# segger_adaptor_v1.net
KiCad netlist of a schematic drawn in EAGLE
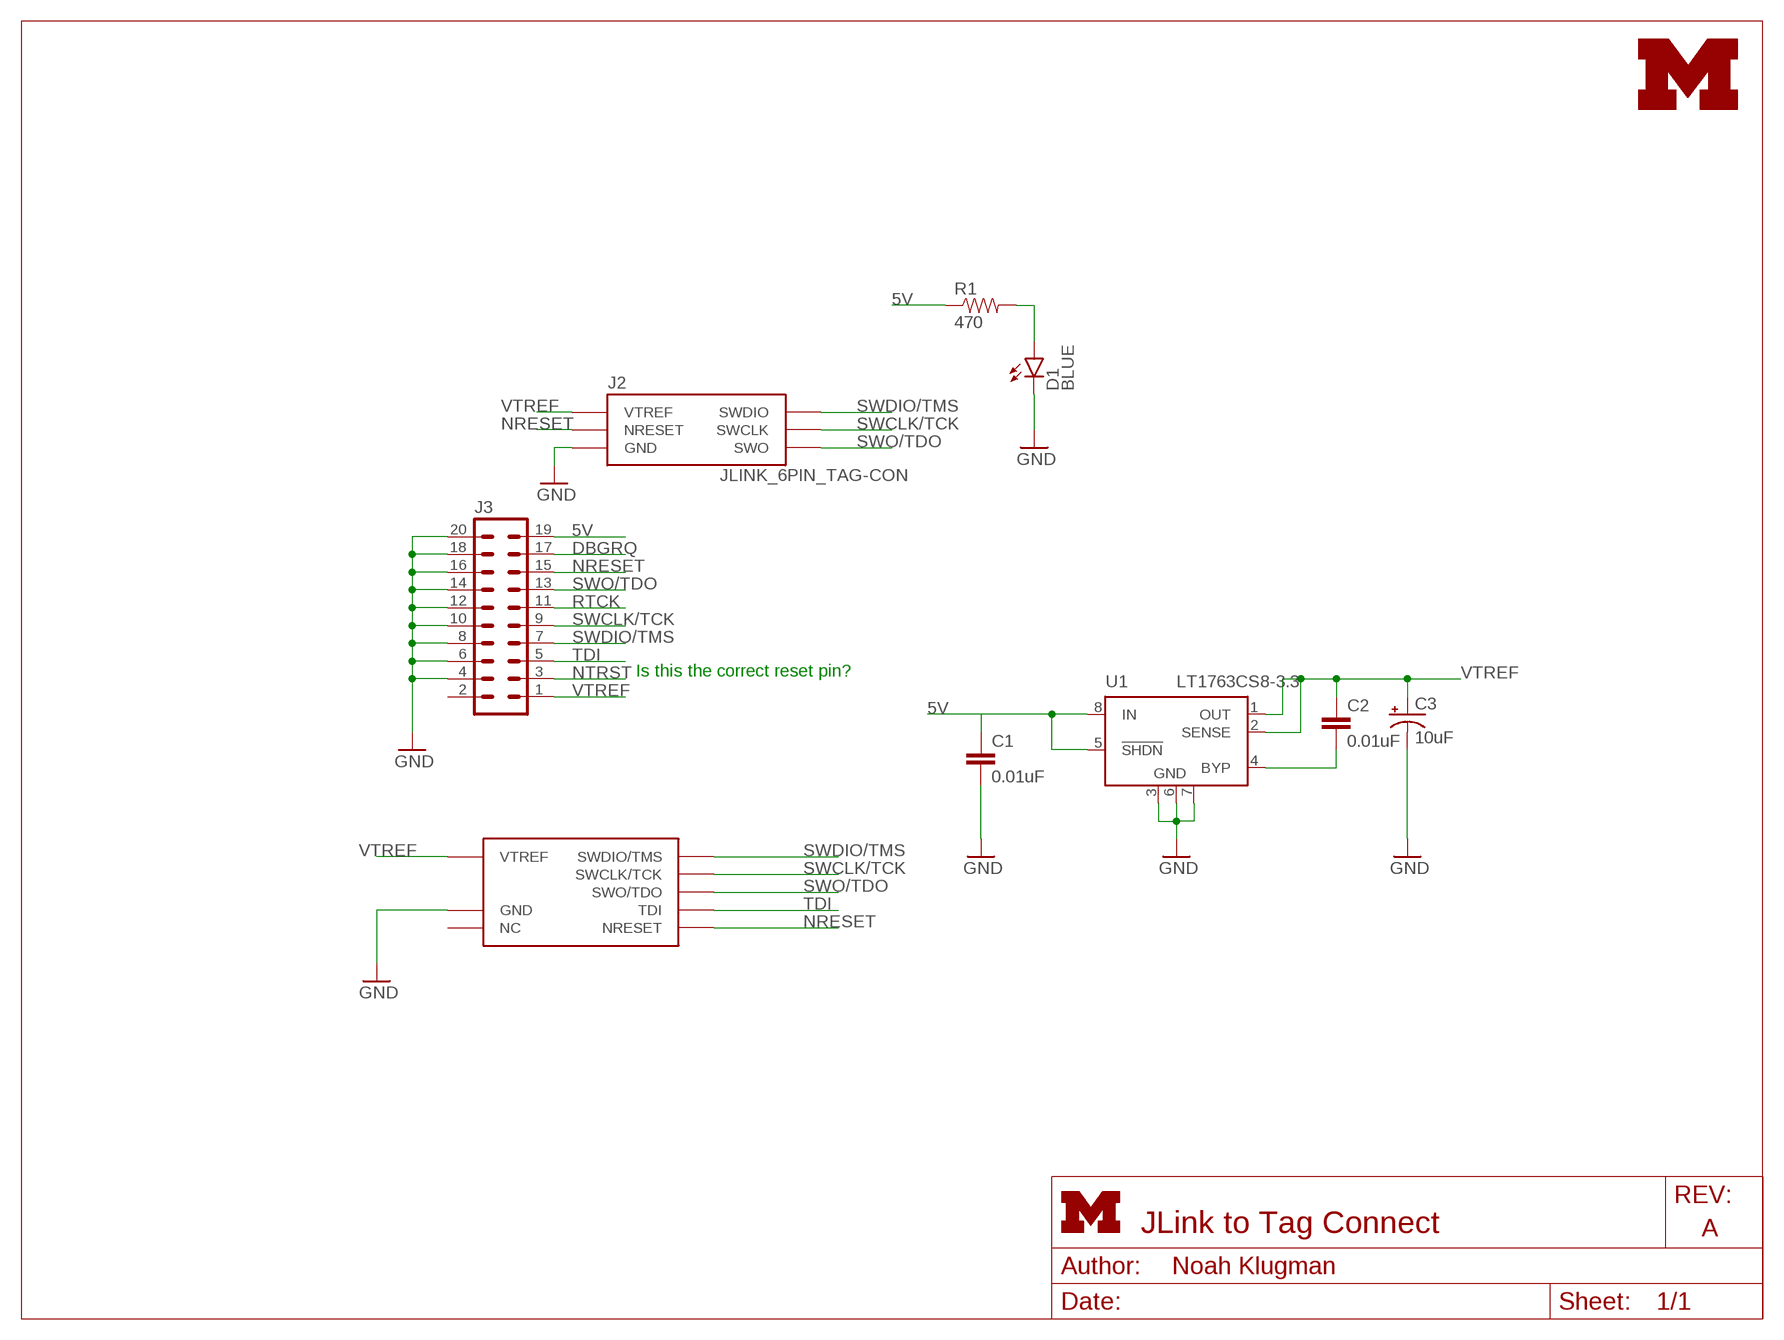
[diagram p0: schematic, sheet 1]

(export (version "E")
  (design (tool "Eeschema 10.0.6"))
  (components
    (comp (ref "C1")
      (value "0.01uF")
      (footprint "eagle-import:C0603")
      (libsource (lib "eagle-import") (part "C-EUC0603"))
    )
    (comp (ref "C2")
      (value "0.01uF")
      (footprint "eagle-import:C0603")
      (libsource (lib "eagle-import") (part "C-EUC0603"))
    )
    (comp (ref "C3")
      (value "10uF")
      (footprint "eagle-import:EIA3216")
      (libsource (lib "eagle-import") (part "CAP_POL1206"))
    )
    (comp (ref "D1")
      (value "BLUE")
      (footprint "eagle-import:LED-0603")
      (libsource (lib "eagle-import") (part "LED-BLUE0603"))
    )
    (comp (ref "J1")
      (value "PINHD-2X5/0.050-NO7")
      (footprint "eagle-import:2X5-0.050-NO7")
      (libsource (lib "eagle-import") (part "PINHD-2X5/0.050-NO7"))
    )
    (comp (ref "J2")
      (value "JLINK_6PIN_TAG-CON")
      (footprint "eagle-import:2X3_MALE_SHROUDED_0.100")
      (libsource (lib "eagle-import") (part "JLINK_6PIN_TAG-CON"))
    )
    (comp (ref "J3")
      (value "ML20")
      (footprint "eagle-import:ML20")
      (libsource (lib "eagle-import") (part "ML20"))
    )
    (comp (ref "LOGO1")
      (value "UMICH_SOLID_SMALL+")
      (footprint "eagle-import:UMICH_SOLID_100MIL")
      (libsource (lib "eagle-import") (part "UMICH_SOLID_SMALL+"))
    )
    (comp (ref "R1")
      (value "470")
      (footprint "eagle-import:0603-RES")
      (libsource (lib "eagle-import") (part "RESISTOR0603-RES"))
    )
    (comp (ref "U1")
      (value "LT1763CS8-3.3")
      (footprint "eagle-import:SOIC8")
      (libsource (lib "eagle-import") (part "LT1763CS8-3.3"))
    )
  )
  (nets
    (net (code "1") (name "/5V") (class "Default")
      (node (ref "C1") (pin "1") (pinfunction "1_1") (pintype "passive"))
      (node (ref "J3") (pin "19") (pinfunction "19_19") (pintype "passive"))
      (node (ref "R1") (pin "1") (pinfunction "1_1") (pintype "passive"))
      (node (ref "U1") (pin "5") (pinfunction "~{SHDN}_5") (pintype "input"))
      (node (ref "U1") (pin "8") (pinfunction "IN_8") (pintype "input"))
    )
    (net (code "2") (name "/DBGRQ") (class "Default")
      (node (ref "J3") (pin "17") (pinfunction "17_17") (pintype "passive"))
    )
    (net (code "3") (name "/NRESET") (class "Default")
      (node (ref "J1") (pin "NRESET") (pinfunction "NRESET_NRESET") (pintype "bidirectional"))
      (node (ref "J2") (pin "3") (pinfunction "NRESET_3") (pintype "bidirectional"))
      (node (ref "J3") (pin "15") (pinfunction "15_15") (pintype "passive"))
    )
    (net (code "4") (name "/NTRST") (class "Default")
      (node (ref "J3") (pin "3") (pinfunction "3_3") (pintype "passive"))
    )
    (net (code "5") (name "/RTCK") (class "Default")
      (node (ref "J3") (pin "11") (pinfunction "11_11") (pintype "passive"))
    )
    (net (code "6") (name "/SWCLK{slash}TCK") (class "Default")
      (node (ref "J1") (pin "SWCLK/TCK") (pinfunction "SWCLK/TCK_SWCLK/TCK") (pintype "bidirectional"))
      (node (ref "J2") (pin "4") (pinfunction "SWCLK_4") (pintype "bidirectional"))
      (node (ref "J3") (pin "9") (pinfunction "9_9") (pintype "passive"))
    )
    (net (code "7") (name "/SWDIO{slash}TMS") (class "Default")
      (node (ref "J1") (pin "SWDIO/TMS") (pinfunction "SWDIO/TMS_SWDIO/TMS") (pintype "bidirectional"))
      (node (ref "J2") (pin "2") (pinfunction "SWDIO_2") (pintype "bidirectional"))
      (node (ref "J3") (pin "7") (pinfunction "7_7") (pintype "passive"))
    )
    (net (code "8") (name "/SWO{slash}TDO") (class "Default")
      (node (ref "J1") (pin "SWO/TDO") (pinfunction "SWO/TDO_SWO/TDO") (pintype "bidirectional"))
      (node (ref "J2") (pin "6") (pinfunction "SWO_6") (pintype "bidirectional"))
      (node (ref "J3") (pin "13") (pinfunction "13_13") (pintype "passive"))
    )
    (net (code "9") (name "/TDI") (class "Default")
      (node (ref "J1") (pin "TDI") (pinfunction "TDI_TDI") (pintype "bidirectional"))
      (node (ref "J3") (pin "5") (pinfunction "5_5") (pintype "passive"))
    )
    (net (code "10") (name "/VTREF") (class "Default")
      (node (ref "C2") (pin "1") (pinfunction "1_1") (pintype "passive"))
      (node (ref "C3") (pin "A") (pinfunction "+_A") (pintype "passive"))
      (node (ref "J1") (pin "VTREF") (pinfunction "VTREF_VTREF") (pintype "bidirectional"))
      (node (ref "J2") (pin "1") (pinfunction "VTREF_1") (pintype "bidirectional"))
      (node (ref "J3") (pin "1") (pinfunction "1_1") (pintype "passive"))
      (node (ref "U1") (pin "1") (pinfunction "OUT_1") (pintype "passive"))
      (node (ref "U1") (pin "2") (pinfunction "SENSE_2") (pintype "input"))
    )
    (net (code "11") (name "GND") (class "Default")
      (node (ref "C1") (pin "2") (pinfunction "2_2") (pintype "passive"))
      (node (ref "C3") (pin "C") (pinfunction "-_C") (pintype "passive"))
      (node (ref "D1") (pin "C") (pinfunction "C_C") (pintype "passive"))
      (node (ref "J1") (pin "GND@1") (pinfunction "GND_GND@1") (pintype "bidirectional"))
      (node (ref "J1") (pin "GND@2") (pinfunction "GND_GND@2") (pintype "bidirectional"))
      (node (ref "J2") (pin "5") (pinfunction "GND_5") (pintype "bidirectional"))
      (node (ref "J3") (pin "10") (pinfunction "10_10") (pintype "passive"))
      (node (ref "J3") (pin "12") (pinfunction "12_12") (pintype "passive"))
      (node (ref "J3") (pin "14") (pinfunction "14_14") (pintype "passive"))
      (node (ref "J3") (pin "16") (pinfunction "16_16") (pintype "passive"))
      (node (ref "J3") (pin "18") (pinfunction "18_18") (pintype "passive"))
      (node (ref "J3") (pin "20") (pinfunction "20_20") (pintype "passive"))
      (node (ref "J3") (pin "4") (pinfunction "4_4") (pintype "passive"))
      (node (ref "J3") (pin "6") (pinfunction "6_6") (pintype "passive"))
      (node (ref "J3") (pin "8") (pinfunction "8_8") (pintype "passive"))
      (node (ref "U1") (pin "3") (pinfunction "GND_3") (pintype "power_in"))
      (node (ref "U1") (pin "6") (pinfunction "GND_6") (pintype "power_in"))
      (node (ref "U1") (pin "7") (pinfunction "GND_7") (pintype "power_in"))
    )
    (net (code "12") (name "Net-(D1-PadA)") (class "Default")
      (node (ref "D1") (pin "A") (pinfunction "A_A") (pintype "passive"))
      (node (ref "R1") (pin "2") (pinfunction "2_2") (pintype "passive"))
    )
    (net (code "13") (name "Net-(U1-BYP)") (class "Default")
      (node (ref "C2") (pin "2") (pinfunction "2_2") (pintype "passive"))
      (node (ref "U1") (pin "4") (pinfunction "BYP_4") (pintype "input"))
    )
    (net (code "14") (name "unconnected-(J1-PadNC)") (class "Default")
      (node (ref "J1") (pin "NC") (pinfunction "NC_NC") (pintype "bidirectional"))
    )
    (net (code "15") (name "unconnected-(J3-Pad2)") (class "Default")
      (node (ref "J3") (pin "2") (pinfunction "2_2") (pintype "passive"))
    )
  )
)
